# motherboard.net
KiCad netlist of a schematic drawn in EAGLE
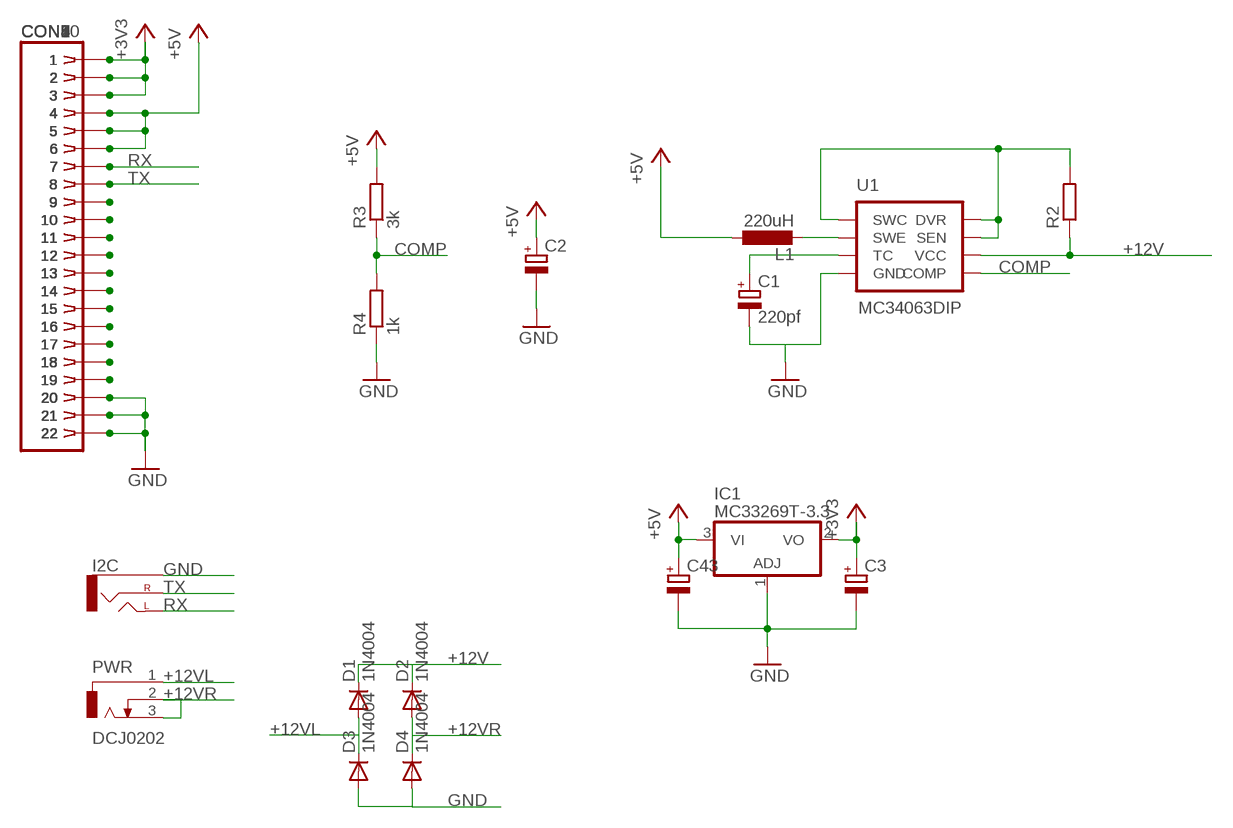
[diagram p0: schematic, sheet 1]

(export (version "E")
  (design (tool "Eeschema 10.0.6"))
  (components
    (comp (ref "C1")
      (value "220pf")
      (footprint "eagle-import:E3,5-8")
      (libsource (lib "eagle-import") (part "CPOL-EUE3.5-8"))
    )
    (comp (ref "C2")
      (value "CPOL-EUE3.5-8")
      (footprint "eagle-import:E3,5-8")
      (libsource (lib "eagle-import") (part "CPOL-EUE3.5-8"))
    )
    (comp (ref "C3")
      (value "CPOL-EUE2-4")
      (footprint "eagle-import:E2-4")
      (libsource (lib "eagle-import") (part "CPOL-EUE2-4"))
    )
    (comp (ref "C43")
      (value "CPOL-EUE2-4")
      (footprint "eagle-import:E2-4")
      (libsource (lib "eagle-import") (part "CPOL-EUE2-4"))
    )
    (comp (ref "CON1")
      (value "SIMM22")
      (footprint "eagle-import:SIMM22")
      (libsource (lib "eagle-import") (part "SIMM22"))
    )
    (comp (ref "CON2")
      (value "SIMM22")
      (footprint "eagle-import:SIMM22")
      (libsource (lib "eagle-import") (part "SIMM22"))
    )
    (comp (ref "CON3")
      (value "SIMM22")
      (footprint "eagle-import:SIMM22")
      (libsource (lib "eagle-import") (part "SIMM22"))
    )
    (comp (ref "CON4")
      (value "SIMM22")
      (footprint "eagle-import:SIMM22")
      (libsource (lib "eagle-import") (part "SIMM22"))
    )
    (comp (ref "CON5")
      (value "SIMM22")
      (footprint "eagle-import:SIMM22")
      (libsource (lib "eagle-import") (part "SIMM22"))
    )
    (comp (ref "CON6")
      (value "SIMM22")
      (footprint "eagle-import:SIMM22")
      (libsource (lib "eagle-import") (part "SIMM22"))
    )
    (comp (ref "CON7")
      (value "SIMM22")
      (footprint "eagle-import:SIMM22")
      (libsource (lib "eagle-import") (part "SIMM22"))
    )
    (comp (ref "CON8")
      (value "SIMM22")
      (footprint "eagle-import:SIMM22")
      (libsource (lib "eagle-import") (part "SIMM22"))
    )
    (comp (ref "CON9")
      (value "SIMM22")
      (footprint "eagle-import:SIMM22")
      (libsource (lib "eagle-import") (part "SIMM22"))
    )
    (comp (ref "CON10")
      (value "SIMM22")
      (footprint "eagle-import:SIMM22")
      (libsource (lib "eagle-import") (part "SIMM22"))
    )
    (comp (ref "D1")
      (value "1N4004")
      (footprint "eagle-import:DO41-10")
      (libsource (lib "eagle-import") (part "1N4004"))
    )
    (comp (ref "D2")
      (value "1N4004")
      (footprint "eagle-import:DO41-10")
      (libsource (lib "eagle-import") (part "1N4004"))
    )
    (comp (ref "D3")
      (value "1N4004")
      (footprint "eagle-import:DO41-10")
      (libsource (lib "eagle-import") (part "1N4004"))
    )
    (comp (ref "D4")
      (value "1N4004")
      (footprint "eagle-import:DO41-10")
      (libsource (lib "eagle-import") (part "1N4004"))
    )
    (comp (ref "I2C")
      (value "AUDIO-JACKPTH")
      (footprint "eagle-import:AUDIO-JACK")
      (libsource (lib "eagle-import") (part "AUDIO-JACKPTH"))
    )
    (comp (ref "IC1")
      (value "MC33269T-3.3")
      (footprint "eagle-import:TO220V")
      (libsource (lib "eagle-import") (part "MC33269?T-3.3"))
    )
    (comp (ref "L1")
      (value "220uH")
      (footprint "eagle-import:0204_7")
      (libsource (lib "eagle-import") (part "L-EU0204/7"))
    )
    (comp (ref "PWR")
      (value "DCJ0202")
      (footprint "eagle-import:DCJ0202")
      (libsource (lib "eagle-import") (part "DCJ0202"))
    )
    (comp (ref "R2")
      (value "R-EU_0204/7")
      (footprint "eagle-import:0204_7")
      (libsource (lib "eagle-import") (part "R-EU_0204/7"))
    )
    (comp (ref "R3")
      (value "3k")
      (footprint "eagle-import:0204_7")
      (libsource (lib "eagle-import") (part "R-EU_0204/7"))
    )
    (comp (ref "R4")
      (value "1k")
      (footprint "eagle-import:0204_7")
      (libsource (lib "eagle-import") (part "R-EU_0204/7"))
    )
    (comp (ref "U1")
      (value "MC34063DIP")
      (footprint "eagle-import:DIP-08")
      (libsource (lib "eagle-import") (part "MC34063DIP"))
    )
  )
  (nets
    (net (code "1") (name "+3V3") (class "Default")
      (node (ref "C3") (pin "+") (pinfunction "+_+") (pintype "passive"))
      (node (ref "CON1") (pin "1") (pinfunction "1_1") (pintype "passive"))
      (node (ref "CON1") (pin "2") (pinfunction "2_2") (pintype "passive"))
      (node (ref "CON1") (pin "3") (pinfunction "3_3") (pintype "passive"))
      (node (ref "CON10") (pin "1") (pinfunction "1_1") (pintype "passive"))
      (node (ref "CON10") (pin "2") (pinfunction "2_2") (pintype "passive"))
      (node (ref "CON10") (pin "3") (pinfunction "3_3") (pintype "passive"))
      (node (ref "CON2") (pin "1") (pinfunction "1_1") (pintype "passive"))
      (node (ref "CON2") (pin "2") (pinfunction "2_2") (pintype "passive"))
      (node (ref "CON2") (pin "3") (pinfunction "3_3") (pintype "passive"))
      (node (ref "CON3") (pin "1") (pinfunction "1_1") (pintype "passive"))
      (node (ref "CON3") (pin "2") (pinfunction "2_2") (pintype "passive"))
      (node (ref "CON3") (pin "3") (pinfunction "3_3") (pintype "passive"))
      (node (ref "CON4") (pin "1") (pinfunction "1_1") (pintype "passive"))
      (node (ref "CON4") (pin "2") (pinfunction "2_2") (pintype "passive"))
      (node (ref "CON4") (pin "3") (pinfunction "3_3") (pintype "passive"))
      (node (ref "CON5") (pin "1") (pinfunction "1_1") (pintype "passive"))
      (node (ref "CON5") (pin "2") (pinfunction "2_2") (pintype "passive"))
      (node (ref "CON5") (pin "3") (pinfunction "3_3") (pintype "passive"))
      (node (ref "CON6") (pin "1") (pinfunction "1_1") (pintype "passive"))
      (node (ref "CON6") (pin "2") (pinfunction "2_2") (pintype "passive"))
      (node (ref "CON6") (pin "3") (pinfunction "3_3") (pintype "passive"))
      (node (ref "CON7") (pin "1") (pinfunction "1_1") (pintype "passive"))
      (node (ref "CON7") (pin "2") (pinfunction "2_2") (pintype "passive"))
      (node (ref "CON7") (pin "3") (pinfunction "3_3") (pintype "passive"))
      (node (ref "CON8") (pin "1") (pinfunction "1_1") (pintype "passive"))
      (node (ref "CON8") (pin "2") (pinfunction "2_2") (pintype "passive"))
      (node (ref "CON8") (pin "3") (pinfunction "3_3") (pintype "passive"))
      (node (ref "CON9") (pin "1") (pinfunction "1_1") (pintype "passive"))
      (node (ref "CON9") (pin "2") (pinfunction "2_2") (pintype "passive"))
      (node (ref "CON9") (pin "3") (pinfunction "3_3") (pintype "passive"))
      (node (ref "IC1") (pin "2") (pinfunction "VO_2") (pintype "passive"))
    )
    (net (code "2") (name "+5V") (class "Default")
      (node (ref "C2") (pin "+") (pinfunction "+_+") (pintype "passive"))
      (node (ref "C43") (pin "+") (pinfunction "+_+") (pintype "passive"))
      (node (ref "CON1") (pin "4") (pinfunction "4_4") (pintype "passive"))
      (node (ref "CON1") (pin "5") (pinfunction "5_5") (pintype "passive"))
      (node (ref "CON1") (pin "6") (pinfunction "6_6") (pintype "passive"))
      (node (ref "CON10") (pin "4") (pinfunction "4_4") (pintype "passive"))
      (node (ref "CON10") (pin "5") (pinfunction "5_5") (pintype "passive"))
      (node (ref "CON10") (pin "6") (pinfunction "6_6") (pintype "passive"))
      (node (ref "CON2") (pin "4") (pinfunction "4_4") (pintype "passive"))
      (node (ref "CON2") (pin "5") (pinfunction "5_5") (pintype "passive"))
      (node (ref "CON2") (pin "6") (pinfunction "6_6") (pintype "passive"))
      (node (ref "CON3") (pin "4") (pinfunction "4_4") (pintype "passive"))
      (node (ref "CON3") (pin "5") (pinfunction "5_5") (pintype "passive"))
      (node (ref "CON3") (pin "6") (pinfunction "6_6") (pintype "passive"))
      (node (ref "CON4") (pin "4") (pinfunction "4_4") (pintype "passive"))
      (node (ref "CON4") (pin "5") (pinfunction "5_5") (pintype "passive"))
      (node (ref "CON4") (pin "6") (pinfunction "6_6") (pintype "passive"))
      (node (ref "CON5") (pin "4") (pinfunction "4_4") (pintype "passive"))
      (node (ref "CON5") (pin "5") (pinfunction "5_5") (pintype "passive"))
      (node (ref "CON5") (pin "6") (pinfunction "6_6") (pintype "passive"))
      (node (ref "CON6") (pin "4") (pinfunction "4_4") (pintype "passive"))
      (node (ref "CON6") (pin "5") (pinfunction "5_5") (pintype "passive"))
      (node (ref "CON6") (pin "6") (pinfunction "6_6") (pintype "passive"))
      (node (ref "CON7") (pin "4") (pinfunction "4_4") (pintype "passive"))
      (node (ref "CON7") (pin "5") (pinfunction "5_5") (pintype "passive"))
      (node (ref "CON7") (pin "6") (pinfunction "6_6") (pintype "passive"))
      (node (ref "CON8") (pin "4") (pinfunction "4_4") (pintype "passive"))
      (node (ref "CON8") (pin "5") (pinfunction "5_5") (pintype "passive"))
      (node (ref "CON8") (pin "6") (pinfunction "6_6") (pintype "passive"))
      (node (ref "CON9") (pin "4") (pinfunction "4_4") (pintype "passive"))
      (node (ref "CON9") (pin "5") (pinfunction "5_5") (pintype "passive"))
      (node (ref "CON9") (pin "6") (pinfunction "6_6") (pintype "passive"))
      (node (ref "IC1") (pin "3") (pinfunction "VI_3") (pintype "input"))
      (node (ref "L1") (pin "1") (pinfunction "1_1") (pintype "passive"))
      (node (ref "R3") (pin "2") (pinfunction "2_2") (pintype "passive"))
    )
    (net (code "3") (name "/+12V") (class "Default")
      (node (ref "D1") (pin "C") (pinfunction "C_C") (pintype "passive"))
      (node (ref "D2") (pin "C") (pinfunction "C_C") (pintype "passive"))
      (node (ref "R2") (pin "1") (pinfunction "1_1") (pintype "passive"))
      (node (ref "U1") (pin "6") (pinfunction "VCC_6") (pintype "bidirectional"))
    )
    (net (code "4") (name "/+12VL") (class "Default")
      (node (ref "D1") (pin "A") (pinfunction "A_A") (pintype "passive"))
      (node (ref "D3") (pin "C") (pinfunction "C_C") (pintype "passive"))
      (node (ref "PWR") (pin "1") (pinfunction "1_1") (pintype "passive"))
    )
    (net (code "5") (name "/+12VR") (class "Default")
      (node (ref "D2") (pin "A") (pinfunction "A_A") (pintype "passive"))
      (node (ref "D4") (pin "C") (pinfunction "C_C") (pintype "passive"))
      (node (ref "PWR") (pin "2") (pinfunction "2_2") (pintype "passive"))
      (node (ref "PWR") (pin "3") (pinfunction "3_3") (pintype "passive"))
    )
    (net (code "6") (name "/COMP") (class "Default")
      (node (ref "R3") (pin "1") (pinfunction "1_1") (pintype "passive"))
      (node (ref "R4") (pin "2") (pinfunction "2_2") (pintype "passive"))
      (node (ref "U1") (pin "5") (pinfunction "COMP_5") (pintype "bidirectional"))
    )
    (net (code "7") (name "/RX") (class "Default")
      (node (ref "CON1") (pin "7") (pinfunction "7_7") (pintype "passive"))
      (node (ref "CON10") (pin "7") (pinfunction "7_7") (pintype "passive"))
      (node (ref "CON2") (pin "7") (pinfunction "7_7") (pintype "passive"))
      (node (ref "CON3") (pin "7") (pinfunction "7_7") (pintype "passive"))
      (node (ref "CON4") (pin "7") (pinfunction "7_7") (pintype "passive"))
      (node (ref "CON5") (pin "7") (pinfunction "7_7") (pintype "passive"))
      (node (ref "CON6") (pin "7") (pinfunction "7_7") (pintype "passive"))
      (node (ref "CON7") (pin "7") (pinfunction "7_7") (pintype "passive"))
      (node (ref "CON8") (pin "7") (pinfunction "7_7") (pintype "passive"))
      (node (ref "CON9") (pin "7") (pinfunction "7_7") (pintype "passive"))
      (node (ref "I2C") (pin "TIP") (pinfunction "LEFT_TIP") (pintype "bidirectional"))
    )
    (net (code "8") (name "/TX") (class "Default")
      (node (ref "CON1") (pin "8") (pinfunction "8_8") (pintype "passive"))
      (node (ref "CON10") (pin "8") (pinfunction "8_8") (pintype "passive"))
      (node (ref "CON2") (pin "8") (pinfunction "8_8") (pintype "passive"))
      (node (ref "CON3") (pin "8") (pinfunction "8_8") (pintype "passive"))
      (node (ref "CON4") (pin "8") (pinfunction "8_8") (pintype "passive"))
      (node (ref "CON5") (pin "8") (pinfunction "8_8") (pintype "passive"))
      (node (ref "CON6") (pin "8") (pinfunction "8_8") (pintype "passive"))
      (node (ref "CON7") (pin "8") (pinfunction "8_8") (pintype "passive"))
      (node (ref "CON8") (pin "8") (pinfunction "8_8") (pintype "passive"))
      (node (ref "CON9") (pin "8") (pinfunction "8_8") (pintype "passive"))
      (node (ref "I2C") (pin "RING") (pinfunction "RIGHT_RING") (pintype "bidirectional"))
    )
    (net (code "9") (name "GND") (class "Default")
      (node (ref "C1") (pin "-") (pinfunction "-_-") (pintype "passive"))
      (node (ref "C2") (pin "-") (pinfunction "-_-") (pintype "passive"))
      (node (ref "C3") (pin "-") (pinfunction "-_-") (pintype "passive"))
      (node (ref "C43") (pin "-") (pinfunction "-_-") (pintype "passive"))
      (node (ref "CON1") (pin "20") (pinfunction "20_20") (pintype "passive"))
      (node (ref "CON1") (pin "21") (pinfunction "21_21") (pintype "passive"))
      (node (ref "CON1") (pin "22") (pinfunction "22_22") (pintype "passive"))
      (node (ref "CON10") (pin "20") (pinfunction "20_20") (pintype "passive"))
      (node (ref "CON10") (pin "21") (pinfunction "21_21") (pintype "passive"))
      (node (ref "CON10") (pin "22") (pinfunction "22_22") (pintype "passive"))
      (node (ref "CON2") (pin "20") (pinfunction "20_20") (pintype "passive"))
      (node (ref "CON2") (pin "21") (pinfunction "21_21") (pintype "passive"))
      (node (ref "CON2") (pin "22") (pinfunction "22_22") (pintype "passive"))
      (node (ref "CON3") (pin "20") (pinfunction "20_20") (pintype "passive"))
      (node (ref "CON3") (pin "21") (pinfunction "21_21") (pintype "passive"))
      (node (ref "CON3") (pin "22") (pinfunction "22_22") (pintype "passive"))
      (node (ref "CON4") (pin "20") (pinfunction "20_20") (pintype "passive"))
      (node (ref "CON4") (pin "21") (pinfunction "21_21") (pintype "passive"))
      (node (ref "CON4") (pin "22") (pinfunction "22_22") (pintype "passive"))
      (node (ref "CON5") (pin "20") (pinfunction "20_20") (pintype "passive"))
      (node (ref "CON5") (pin "21") (pinfunction "21_21") (pintype "passive"))
      (node (ref "CON5") (pin "22") (pinfunction "22_22") (pintype "passive"))
      (node (ref "CON6") (pin "20") (pinfunction "20_20") (pintype "passive"))
      (node (ref "CON6") (pin "21") (pinfunction "21_21") (pintype "passive"))
      (node (ref "CON6") (pin "22") (pinfunction "22_22") (pintype "passive"))
      (node (ref "CON7") (pin "20") (pinfunction "20_20") (pintype "passive"))
      (node (ref "CON7") (pin "21") (pinfunction "21_21") (pintype "passive"))
      (node (ref "CON7") (pin "22") (pinfunction "22_22") (pintype "passive"))
      (node (ref "CON8") (pin "20") (pinfunction "20_20") (pintype "passive"))
      (node (ref "CON8") (pin "21") (pinfunction "21_21") (pintype "passive"))
      (node (ref "CON8") (pin "22") (pinfunction "22_22") (pintype "passive"))
      (node (ref "CON9") (pin "20") (pinfunction "20_20") (pintype "passive"))
      (node (ref "CON9") (pin "21") (pinfunction "21_21") (pintype "passive"))
      (node (ref "CON9") (pin "22") (pinfunction "22_22") (pintype "passive"))
      (node (ref "D3") (pin "A") (pinfunction "A_A") (pintype "passive"))
      (node (ref "D4") (pin "A") (pinfunction "A_A") (pintype "passive"))
      (node (ref "I2C") (pin "SLEEVE") (pinfunction "SLEEVE_SLEEVE") (pintype "bidirectional"))
      (node (ref "IC1") (pin "1") (pinfunction "ADJ_1") (pintype "input"))
      (node (ref "R4") (pin "1") (pinfunction "1_1") (pintype "passive"))
      (node (ref "U1") (pin "4") (pinfunction "GND_4") (pintype "bidirectional"))
    )
    (net (code "10") (name "Net-(CON1-Pad9)") (class "Default")
      (node (ref "CON1") (pin "9") (pinfunction "9_9") (pintype "passive"))
      (node (ref "CON10") (pin "9") (pinfunction "9_9") (pintype "passive"))
      (node (ref "CON2") (pin "9") (pinfunction "9_9") (pintype "passive"))
      (node (ref "CON3") (pin "9") (pinfunction "9_9") (pintype "passive"))
      (node (ref "CON4") (pin "9") (pinfunction "9_9") (pintype "passive"))
      (node (ref "CON5") (pin "9") (pinfunction "9_9") (pintype "passive"))
      (node (ref "CON6") (pin "9") (pinfunction "9_9") (pintype "passive"))
      (node (ref "CON7") (pin "9") (pinfunction "9_9") (pintype "passive"))
      (node (ref "CON8") (pin "9") (pinfunction "9_9") (pintype "passive"))
      (node (ref "CON9") (pin "9") (pinfunction "9_9") (pintype "passive"))
    )
    (net (code "11") (name "Net-(CON1-Pad10)") (class "Default")
      (node (ref "CON1") (pin "10") (pinfunction "10_10") (pintype "passive"))
      (node (ref "CON10") (pin "10") (pinfunction "10_10") (pintype "passive"))
      (node (ref "CON2") (pin "10") (pinfunction "10_10") (pintype "passive"))
      (node (ref "CON3") (pin "10") (pinfunction "10_10") (pintype "passive"))
      (node (ref "CON4") (pin "10") (pinfunction "10_10") (pintype "passive"))
      (node (ref "CON5") (pin "10") (pinfunction "10_10") (pintype "passive"))
      (node (ref "CON6") (pin "10") (pinfunction "10_10") (pintype "passive"))
      (node (ref "CON7") (pin "10") (pinfunction "10_10") (pintype "passive"))
      (node (ref "CON8") (pin "10") (pinfunction "10_10") (pintype "passive"))
      (node (ref "CON9") (pin "10") (pinfunction "10_10") (pintype "passive"))
    )
    (net (code "12") (name "Net-(CON1-Pad11)") (class "Default")
      (node (ref "CON1") (pin "11") (pinfunction "11_11") (pintype "passive"))
      (node (ref "CON10") (pin "11") (pinfunction "11_11") (pintype "passive"))
      (node (ref "CON2") (pin "11") (pinfunction "11_11") (pintype "passive"))
      (node (ref "CON3") (pin "11") (pinfunction "11_11") (pintype "passive"))
      (node (ref "CON4") (pin "11") (pinfunction "11_11") (pintype "passive"))
      (node (ref "CON5") (pin "11") (pinfunction "11_11") (pintype "passive"))
      (node (ref "CON6") (pin "11") (pinfunction "11_11") (pintype "passive"))
      (node (ref "CON7") (pin "11") (pinfunction "11_11") (pintype "passive"))
      (node (ref "CON8") (pin "11") (pinfunction "11_11") (pintype "passive"))
      (node (ref "CON9") (pin "11") (pinfunction "11_11") (pintype "passive"))
    )
    (net (code "13") (name "Net-(CON1-Pad12)") (class "Default")
      (node (ref "CON1") (pin "12") (pinfunction "12_12") (pintype "passive"))
      (node (ref "CON10") (pin "12") (pinfunction "12_12") (pintype "passive"))
      (node (ref "CON2") (pin "12") (pinfunction "12_12") (pintype "passive"))
      (node (ref "CON3") (pin "12") (pinfunction "12_12") (pintype "passive"))
      (node (ref "CON4") (pin "12") (pinfunction "12_12") (pintype "passive"))
      (node (ref "CON5") (pin "12") (pinfunction "12_12") (pintype "passive"))
      (node (ref "CON6") (pin "12") (pinfunction "12_12") (pintype "passive"))
      (node (ref "CON7") (pin "12") (pinfunction "12_12") (pintype "passive"))
      (node (ref "CON8") (pin "12") (pinfunction "12_12") (pintype "passive"))
      (node (ref "CON9") (pin "12") (pinfunction "12_12") (pintype "passive"))
    )
    (net (code "14") (name "Net-(CON1-Pad13)") (class "Default")
      (node (ref "CON1") (pin "13") (pinfunction "13_13") (pintype "passive"))
      (node (ref "CON10") (pin "13") (pinfunction "13_13") (pintype "passive"))
      (node (ref "CON2") (pin "13") (pinfunction "13_13") (pintype "passive"))
      (node (ref "CON3") (pin "13") (pinfunction "13_13") (pintype "passive"))
      (node (ref "CON4") (pin "13") (pinfunction "13_13") (pintype "passive"))
      (node (ref "CON5") (pin "13") (pinfunction "13_13") (pintype "passive"))
      (node (ref "CON6") (pin "13") (pinfunction "13_13") (pintype "passive"))
      (node (ref "CON7") (pin "13") (pinfunction "13_13") (pintype "passive"))
      (node (ref "CON8") (pin "13") (pinfunction "13_13") (pintype "passive"))
      (node (ref "CON9") (pin "13") (pinfunction "13_13") (pintype "passive"))
    )
    (net (code "15") (name "Net-(CON1-Pad14)") (class "Default")
      (node (ref "CON1") (pin "14") (pinfunction "14_14") (pintype "passive"))
      (node (ref "CON10") (pin "14") (pinfunction "14_14") (pintype "passive"))
      (node (ref "CON2") (pin "14") (pinfunction "14_14") (pintype "passive"))
      (node (ref "CON3") (pin "14") (pinfunction "14_14") (pintype "passive"))
      (node (ref "CON4") (pin "14") (pinfunction "14_14") (pintype "passive"))
      (node (ref "CON5") (pin "14") (pinfunction "14_14") (pintype "passive"))
      (node (ref "CON6") (pin "14") (pinfunction "14_14") (pintype "passive"))
      (node (ref "CON7") (pin "14") (pinfunction "14_14") (pintype "passive"))
      (node (ref "CON8") (pin "14") (pinfunction "14_14") (pintype "passive"))
      (node (ref "CON9") (pin "14") (pinfunction "14_14") (pintype "passive"))
    )
    (net (code "16") (name "Net-(CON1-Pad15)") (class "Default")
      (node (ref "CON1") (pin "15") (pinfunction "15_15") (pintype "passive"))
      (node (ref "CON10") (pin "15") (pinfunction "15_15") (pintype "passive"))
      (node (ref "CON2") (pin "15") (pinfunction "15_15") (pintype "passive"))
      (node (ref "CON3") (pin "15") (pinfunction "15_15") (pintype "passive"))
      (node (ref "CON4") (pin "15") (pinfunction "15_15") (pintype "passive"))
      (node (ref "CON5") (pin "15") (pinfunction "15_15") (pintype "passive"))
      (node (ref "CON6") (pin "15") (pinfunction "15_15") (pintype "passive"))
      (node (ref "CON7") (pin "15") (pinfunction "15_15") (pintype "passive"))
      (node (ref "CON8") (pin "15") (pinfunction "15_15") (pintype "passive"))
      (node (ref "CON9") (pin "15") (pinfunction "15_15") (pintype "passive"))
    )
    (net (code "17") (name "Net-(CON1-Pad16)") (class "Default")
      (node (ref "CON1") (pin "16") (pinfunction "16_16") (pintype "passive"))
      (node (ref "CON10") (pin "16") (pinfunction "16_16") (pintype "passive"))
      (node (ref "CON2") (pin "16") (pinfunction "16_16") (pintype "passive"))
      (node (ref "CON3") (pin "16") (pinfunction "16_16") (pintype "passive"))
      (node (ref "CON4") (pin "16") (pinfunction "16_16") (pintype "passive"))
      (node (ref "CON5") (pin "16") (pinfunction "16_16") (pintype "passive"))
      (node (ref "CON6") (pin "16") (pinfunction "16_16") (pintype "passive"))
      (node (ref "CON7") (pin "16") (pinfunction "16_16") (pintype "passive"))
      (node (ref "CON8") (pin "16") (pinfunction "16_16") (pintype "passive"))
      (node (ref "CON9") (pin "16") (pinfunction "16_16") (pintype "passive"))
    )
    (net (code "18") (name "Net-(CON1-Pad17)") (class "Default")
      (node (ref "CON1") (pin "17") (pinfunction "17_17") (pintype "passive"))
      (node (ref "CON10") (pin "17") (pinfunction "17_17") (pintype "passive"))
      (node (ref "CON2") (pin "17") (pinfunction "17_17") (pintype "passive"))
      (node (ref "CON3") (pin "17") (pinfunction "17_17") (pintype "passive"))
      (node (ref "CON4") (pin "17") (pinfunction "17_17") (pintype "passive"))
      (node (ref "CON5") (pin "17") (pinfunction "17_17") (pintype "passive"))
      (node (ref "CON6") (pin "17") (pinfunction "17_17") (pintype "passive"))
      (node (ref "CON7") (pin "17") (pinfunction "17_17") (pintype "passive"))
      (node (ref "CON8") (pin "17") (pinfunction "17_17") (pintype "passive"))
      (node (ref "CON9") (pin "17") (pinfunction "17_17") (pintype "passive"))
    )
    (net (code "19") (name "Net-(CON1-Pad18)") (class "Default")
      (node (ref "CON1") (pin "18") (pinfunction "18_18") (pintype "passive"))
      (node (ref "CON10") (pin "18") (pinfunction "18_18") (pintype "passive"))
      (node (ref "CON2") (pin "18") (pinfunction "18_18") (pintype "passive"))
      (node (ref "CON3") (pin "18") (pinfunction "18_18") (pintype "passive"))
      (node (ref "CON4") (pin "18") (pinfunction "18_18") (pintype "passive"))
      (node (ref "CON5") (pin "18") (pinfunction "18_18") (pintype "passive"))
      (node (ref "CON6") (pin "18") (pinfunction "18_18") (pintype "passive"))
      (node (ref "CON7") (pin "18") (pinfunction "18_18") (pintype "passive"))
      (node (ref "CON8") (pin "18") (pinfunction "18_18") (pintype "passive"))
      (node (ref "CON9") (pin "18") (pinfunction "18_18") (pintype "passive"))
    )
    (net (code "20") (name "Net-(CON1-Pad19)") (class "Default")
      (node (ref "CON1") (pin "19") (pinfunction "19_19") (pintype "passive"))
      (node (ref "CON10") (pin "19") (pinfunction "19_19") (pintype "passive"))
      (node (ref "CON2") (pin "19") (pinfunction "19_19") (pintype "passive"))
      (node (ref "CON3") (pin "19") (pinfunction "19_19") (pintype "passive"))
      (node (ref "CON4") (pin "19") (pinfunction "19_19") (pintype "passive"))
      (node (ref "CON5") (pin "19") (pinfunction "19_19") (pintype "passive"))
      (node (ref "CON6") (pin "19") (pinfunction "19_19") (pintype "passive"))
      (node (ref "CON7") (pin "19") (pinfunction "19_19") (pintype "passive"))
      (node (ref "CON8") (pin "19") (pinfunction "19_19") (pintype "passive"))
      (node (ref "CON9") (pin "19") (pinfunction "19_19") (pintype "passive"))
    )
    (net (code "21") (name "Net-(U1-DVR)") (class "Default")
      (node (ref "R2") (pin "2") (pinfunction "2_2") (pintype "passive"))
      (node (ref "U1") (pin "1") (pinfunction "SWC_1") (pintype "bidirectional"))
      (node (ref "U1") (pin "7") (pinfunction "SEN_7") (pintype "bidirectional"))
      (node (ref "U1") (pin "8") (pinfunction "DVR_8") (pintype "bidirectional"))
    )
    (net (code "22") (name "Net-(U1-SWE)") (class "Default")
      (node (ref "L1") (pin "2") (pinfunction "2_2") (pintype "passive"))
      (node (ref "U1") (pin "2") (pinfunction "SWE_2") (pintype "bidirectional"))
    )
    (net (code "23") (name "Net-(U1-TC)") (class "Default")
      (node (ref "C1") (pin "+") (pinfunction "+_+") (pintype "passive"))
      (node (ref "U1") (pin "3") (pinfunction "TC_3") (pintype "bidirectional"))
    )
  )
)
